# KeyBoard.net
KiCad netlist of a schematic drawn in Altium Designer
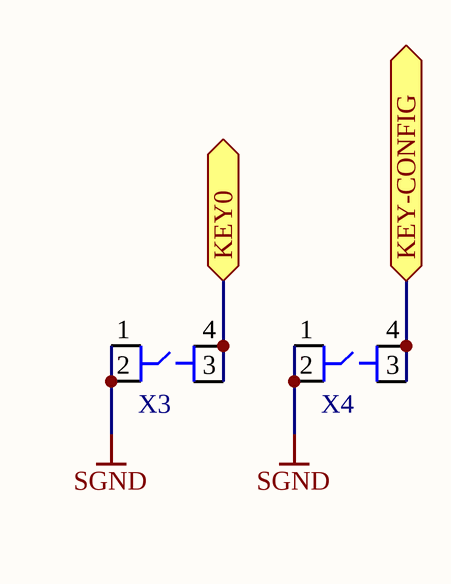
[diagram p0: KeyBoard.SchDoc]

(export (version "E")
  (design (tool "Eeschema 10.0.6"))
  (components
    (comp (ref "X3")
      (value "TACT0606")
      (footprint "TACT0606")
      (description "Tact switch 6x6mm")
      (libsource (lib "MCounter_Common") (part "TACT0606"))
    )
    (comp (ref "X4")
      (value "TACT0606")
      (footprint "TACT0606")
      (description "Tact switch 6x6mm")
      (libsource (lib "MCounter_Common") (part "TACT0606"))
    )
  )
  (nets
    (net (code "1") (name "/KEY-CONFIG") (class "Default")
      (node (ref "X4") (pin "3") (pinfunction "3_3") (pintype "passive"))
      (node (ref "X4") (pin "4") (pinfunction "4_4") (pintype "passive"))
    )
    (net (code "2") (name "/KEY0") (class "Default")
      (node (ref "X3") (pin "3") (pinfunction "3_3") (pintype "passive"))
      (node (ref "X3") (pin "4") (pinfunction "4_4") (pintype "passive"))
    )
    (net (code "3") (name "SGND") (class "Default")
      (node (ref "X3") (pin "1") (pinfunction "1_1") (pintype "passive"))
      (node (ref "X3") (pin "2") (pinfunction "2_2") (pintype "passive"))
      (node (ref "X4") (pin "1") (pinfunction "1_1") (pintype "passive"))
      (node (ref "X4") (pin "2") (pinfunction "2_2") (pintype "passive"))
    )
  )
)
